# Oscilador.net
KiCad netlist of a schematic drawn in Altium Designer
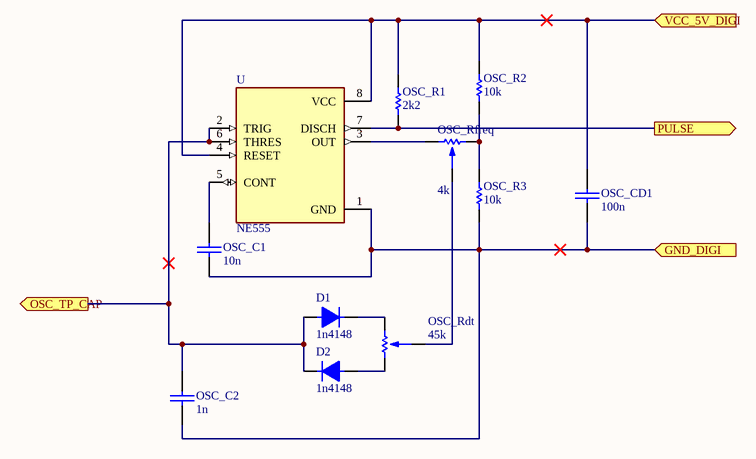
[diagram p0: Oscilador.SchDoc]

(export (version "E")
  (design (tool "Eeschema 10.0.6"))
  (components
    (comp (ref "D1") (value "1n4148") (footprint "DO41") (libsource (lib "LIBEBAL") (part "DIODO")))
    (comp (ref "D2") (value "1n4148") (footprint "DO41") (libsource (lib "LIBEBAL") (part "DIODO")))
    (comp (ref "OSC_C1") (value "10n") (footprint "CAP200") (libsource (lib "LIBEBAL") (part "CAP")))
    (comp (ref "OSC_C2") (value "1n") (footprint "CAP200") (libsource (lib "LIBEBAL") (part "CAP")))
    (comp (ref "OSC_CD1") (value "100n") (footprint "CAP200") (libsource (lib "LIBEBAL") (part "CAP")))
    (comp (ref "OSC_R1") (value "2k2") (footprint "RES400") (libsource (lib "LIBEBAL") (part "RES")))
    (comp (ref "OSC_R2") (value "10k") (footprint "RES400") (libsource (lib "LIBEBAL") (part "RES")))
    (comp (ref "OSC_R3") (value "10k") (footprint "RES400") (libsource (lib "LIBEBAL") (part "RES")))
    (comp (ref "OSC_Rdt")
      (value "45k")
      (footprint "POTENCIOMETRO")
      (libsource (lib "LIBEBAL") (part "POTENCIOMETRO"))
    )
    (comp (ref "OSC_Rfreq")
      (value "4k")
      (footprint "POTENCIOMETRO")
      (libsource (lib "LIBEBAL") (part "POTENCIOMETRO"))
    )
    (comp (ref "U")
      (value "NE555")
      (footprint "DIP794W45P254L1060H508Q8")
      (description "555 Type, Timer/Oscillator _Single_ IC 100kHz 8-SOIC")
      (fields (field (name "MF") "Texas Instruments"))
      (libsource (lib "NE555") (part "NE555"))
    )
  )
  (nets
    (net (code "1") (name "/GND_DIGI") (class "Default")
      (node (ref "OSC_C1") (pin "2") (pinfunction "2_2") (pintype "passive"))
      (node (ref "OSC_C2") (pin "2") (pinfunction "2_2") (pintype "passive"))
      (node (ref "OSC_CD1") (pin "2") (pinfunction "2_2") (pintype "passive"))
      (node (ref "OSC_R3") (pin "1") (pinfunction "1_1") (pintype "passive"))
      (node (ref "U") (pin "1") (pinfunction "GND_1") (pintype "power_in"))
    )
    (net (code "2") (name "/OSC_TP_CAP") (class "Default")
      (node (ref "D1") (pin "1") (pinfunction "1_1") (pintype "passive"))
      (node (ref "D2") (pin "2") (pinfunction "2_2") (pintype "passive"))
      (node (ref "OSC_C2") (pin "1") (pinfunction "1_1") (pintype "passive"))
      (node (ref "U") (pin "2") (pinfunction "TRIG_2") (pintype "input"))
      (node (ref "U") (pin "6") (pinfunction "THRES_6") (pintype "input"))
    )
    (net (code "3") (name "/PULSE") (class "Default")
      (node (ref "OSC_R1") (pin "1") (pinfunction "1_1") (pintype "passive"))
      (node (ref "U") (pin "7") (pinfunction "DISCH_7") (pintype "output"))
    )
    (net (code "4") (name "/VCC_5V_DIGI") (class "Default")
      (node (ref "OSC_CD1") (pin "1") (pinfunction "1_1") (pintype "passive"))
      (node (ref "OSC_R1") (pin "2") (pinfunction "2_2") (pintype "passive"))
      (node (ref "OSC_R2") (pin "2") (pinfunction "2_2") (pintype "passive"))
      (node (ref "U") (pin "4") (pinfunction "RESET_4") (pintype "input"))
      (node (ref "U") (pin "8") (pinfunction "VCC_8") (pintype "power_in"))
    )
    (net (code "5") (name "Net-(D1-Pad2)") (class "Default")
      (node (ref "D1") (pin "2") (pinfunction "2_2") (pintype "passive"))
      (node (ref "OSC_Rdt") (pin "1") (pinfunction "1_1") (pintype "passive"))
    )
    (net (code "6") (name "Net-(D2-Pad1)") (class "Default")
      (node (ref "D2") (pin "1") (pinfunction "1_1") (pintype "passive"))
      (node (ref "OSC_Rdt") (pin "3") (pinfunction "3_3") (pintype "passive"))
    )
    (net (code "7") (name "Net-(OSC_R2-Pad1)") (class "Default")
      (node (ref "OSC_R2") (pin "1") (pinfunction "1_1") (pintype "passive"))
      (node (ref "OSC_R3") (pin "2") (pinfunction "2_2") (pintype "passive"))
      (node (ref "OSC_Rfreq") (pin "1") (pinfunction "1_1") (pintype "passive"))
    )
    (net (code "8") (name "Net-(OSC_Rdt-Pad2)") (class "Default")
      (node (ref "OSC_Rdt") (pin "2") (pinfunction "2_2") (pintype "passive"))
      (node (ref "OSC_Rfreq") (pin "2") (pinfunction "2_2") (pintype "passive"))
    )
    (net (code "9") (name "Net-(U-CONT)") (class "Default")
      (node (ref "OSC_C1") (pin "1") (pinfunction "1_1") (pintype "passive"))
      (node (ref "U") (pin "5") (pinfunction "CONT_5") (pintype "bidirectional"))
    )
    (net (code "10") (name "Net-(U-OUT)") (class "Default")
      (node (ref "OSC_Rfreq") (pin "3") (pinfunction "3_3") (pintype "passive"))
      (node (ref "U") (pin "3") (pinfunction "OUT_3") (pintype "output"))
    )
  )
)
